# displayboard.net
KiCad netlist of a schematic drawn in EAGLE
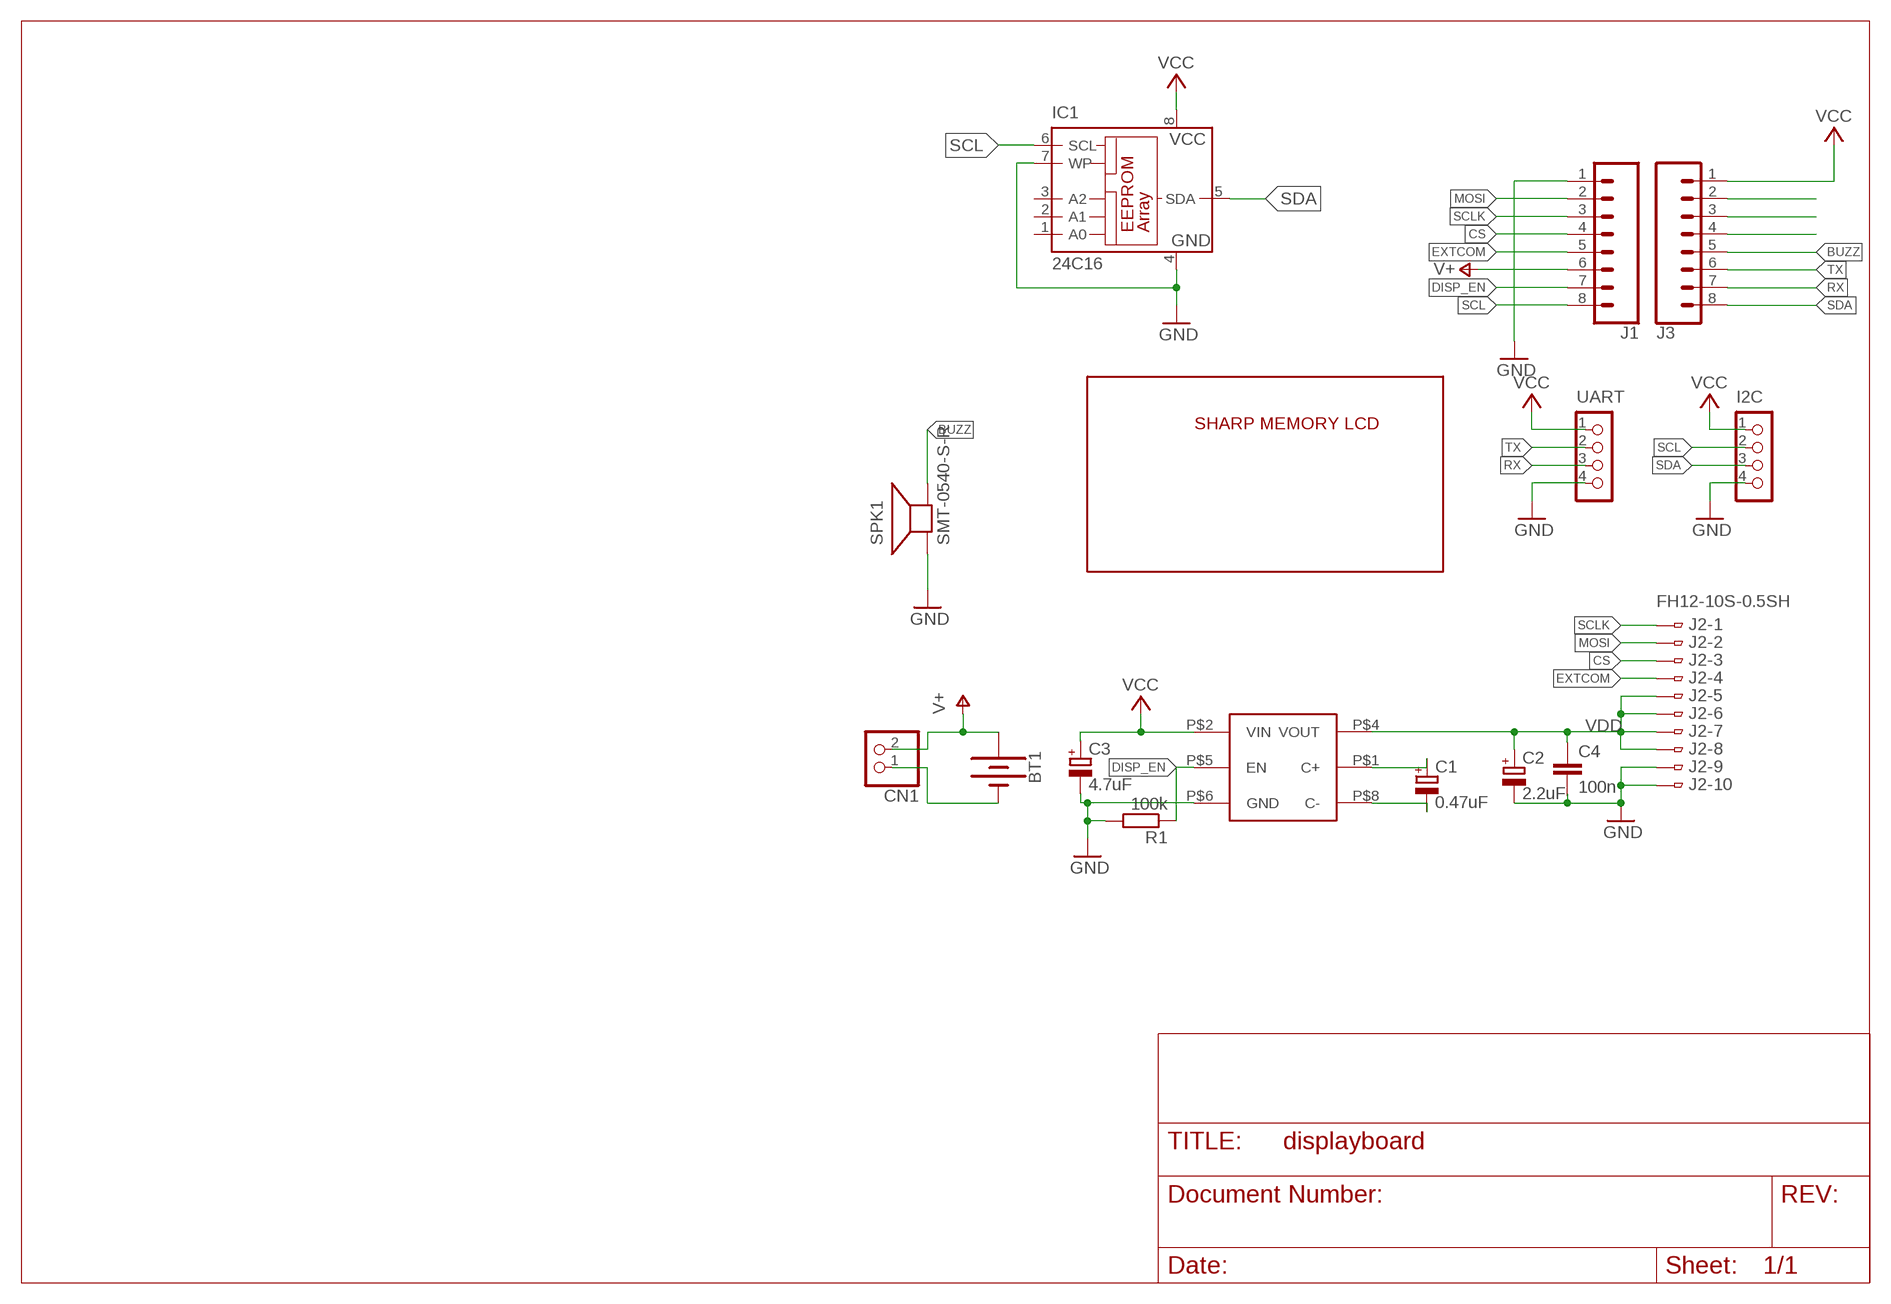
[diagram p0: schematic, sheet 1]

(export (version "E")
  (design (tool "Eeschema 10.0.6"))
  (components
    (comp (ref "BT1")
      (value "BATTERY-18650")
      (footprint "eagle-import:BATTERY_18650-HOLDER")
      (libsource (lib "eagle-import") (part "BATTERY-18650"))
    )
    (comp (ref "C1")
      (value "0.47uF")
      (footprint "eagle-import:C_6032-28R")
      (libsource (lib "eagle-import") (part "CPOL-EUC/6032-28R"))
    )
    (comp (ref "C2")
      (value "2.2uF")
      (footprint "eagle-import:C_6032-28R")
      (libsource (lib "eagle-import") (part "CPOL-EUC/6032-28R"))
    )
    (comp (ref "C3")
      (value "4.7uF")
      (footprint "eagle-import:C_6032-28R")
      (libsource (lib "eagle-import") (part "CPOL-EUC/6032-28R"))
    )
    (comp (ref "C4")
      (value "100n")
      (footprint "eagle-import:C1206K")
      (libsource (lib "eagle-import") (part "C-EUC1206K"))
    )
    (comp (ref "CN1")
      (value "PINHD-1X2")
      (footprint "eagle-import:1X02")
      (libsource (lib "eagle-import") (part "PINHD-1X2"))
    )
    (comp (ref "I2C")
      (value "CON_HEADER_1X04")
      (footprint "eagle-import:M1X4")
      (libsource (lib "eagle-import") (part "CON_HEADER_1X04"))
    )
    (comp (ref "IC1")
      (value "24C16")
      (footprint "eagle-import:SO-08")
      (fields (field (name "MPN") "M24C04-WMN6P"))
      (libsource (lib "eagle-import") (part "24CSN04"))
    )
    (comp (ref "J1")
      (value "CONN_08SMD-COMBO-FEMALE")
      (footprint "eagle-import:1X08_SMD_COMBINED")
      (libsource (lib "eagle-import") (part "CONN_08SMD-COMBO-FEMALE"))
    )
    (comp (ref "J2")
      (value "FH12-10S-0.5SH")
      (footprint "eagle-import:FH12-10S-0.5SH")
      (fields (field (name "MPN") "FH12-10S-0.5SH(55)"))
      (libsource (lib "eagle-import") (part "FH12-10S-0.5SH"))
    )
    (comp (ref "J3")
      (value "CONN_08SMD-COMBO-FEMALE")
      (footprint "eagle-import:1X08_SMD_COMBINED")
      (libsource (lib "eagle-import") (part "CONN_08SMD-COMBO-FEMALE"))
    )
    (comp (ref "R1")
      (value "100k")
      (footprint "eagle-import:R0805")
      (libsource (lib "eagle-import") (part "R-EU_R0805"))
    )
    (comp (ref "SPK1")
      (value "SMT-0540-S-R")
      (footprint "eagle-import:SMT-0540-S-R")
      (libsource (lib "eagle-import") (part "SMT-0540-S-R"))
    )
    (comp (ref "U$1")
      (value "S8821")
      (footprint "eagle-import:SNT-8A")
      (libsource (lib "eagle-import") (part "S8821"))
    )
    (comp (ref "U$2")
      (value "MEMORYLCD")
      (footprint "eagle-import:LS027B7DH01")
      (libsource (lib "eagle-import") (part "MEMORYLCD"))
    )
    (comp (ref "UART")
      (value "CON_HEADER_1X04")
      (footprint "eagle-import:M1X4")
      (libsource (lib "eagle-import") (part "CON_HEADER_1X04"))
    )
  )
  (nets
    (net (code "1") (name "/VDD") (class "Default")
      (node (ref "C2") (pin "+") (pinfunction "+_+") (pintype "passive"))
      (node (ref "C4") (pin "1") (pinfunction "1_1") (pintype "passive"))
      (node (ref "J2") (pin "5") (pinfunction "1_5") (pintype "passive"))
      (node (ref "J2") (pin "6") (pinfunction "1_6") (pintype "passive"))
      (node (ref "J2") (pin "7") (pinfunction "1_7") (pintype "passive"))
      (node (ref "J2") (pin "8") (pinfunction "1_8") (pintype "passive"))
      (node (ref "U$1") (pin "P$4") (pinfunction "VOUT_P$4") (pintype "bidirectional"))
    )
    (net (code "2") (name "BUZZ") (class "Default")
      (node (ref "J3") (pin "5") (pinfunction "5_5") (pintype "passive"))
      (node (ref "SPK1") (pin "+") (pinfunction "-_+") (pintype "passive"))
    )
    (net (code "3") (name "CS") (class "Default")
      (node (ref "J1") (pin "4") (pinfunction "4_4") (pintype "passive"))
      (node (ref "J2") (pin "3") (pinfunction "1_3") (pintype "passive"))
    )
    (net (code "4") (name "DISP_EN") (class "Default")
      (node (ref "J1") (pin "7") (pinfunction "7_7") (pintype "passive"))
      (node (ref "R1") (pin "1") (pinfunction "1_1") (pintype "passive"))
      (node (ref "U$1") (pin "P$5") (pinfunction "EN_P$5") (pintype "bidirectional"))
    )
    (net (code "5") (name "EXTCOM") (class "Default")
      (node (ref "J1") (pin "5") (pinfunction "5_5") (pintype "passive"))
      (node (ref "J2") (pin "4") (pinfunction "1_4") (pintype "passive"))
    )
    (net (code "6") (name "GND") (class "Default")
      (node (ref "C2") (pin "-") (pinfunction "-_-") (pintype "passive"))
      (node (ref "C3") (pin "-") (pinfunction "-_-") (pintype "passive"))
      (node (ref "C4") (pin "2") (pinfunction "2_2") (pintype "passive"))
      (node (ref "I2C") (pin "4") (pinfunction "4_4") (pintype "bidirectional"))
      (node (ref "IC1") (pin "4") (pinfunction "GND_4") (pintype "power_in"))
      (node (ref "IC1") (pin "7") (pinfunction "WP_7") (pintype "input"))
      (node (ref "J1") (pin "1") (pinfunction "1_1") (pintype "passive"))
      (node (ref "J2") (pin "10") (pinfunction "1_10") (pintype "passive"))
      (node (ref "J2") (pin "9") (pinfunction "1_9") (pintype "passive"))
      (node (ref "R1") (pin "2") (pinfunction "2_2") (pintype "passive"))
      (node (ref "SPK1") (pin "-") (pinfunction "+_-") (pintype "passive"))
      (node (ref "U$1") (pin "P$6") (pinfunction "GND_P$6") (pintype "bidirectional"))
      (node (ref "UART") (pin "4") (pinfunction "4_4") (pintype "bidirectional"))
    )
    (net (code "7") (name "MOSI") (class "Default")
      (node (ref "J1") (pin "2") (pinfunction "2_2") (pintype "passive"))
      (node (ref "J2") (pin "2") (pinfunction "1_2") (pintype "passive"))
    )
    (net (code "8") (name "Net-(BT1--)") (class "Default")
      (node (ref "BT1") (pin "GND@1") (pinfunction "-_GND@1") (pintype "power_in"))
      (node (ref "CN1") (pin "1") (pinfunction "1_1") (pintype "passive"))
    )
    (net (code "9") (name "Net-(U$1-C+)") (class "Default")
      (node (ref "C1") (pin "+") (pinfunction "+_+") (pintype "passive"))
      (node (ref "U$1") (pin "P$1") (pinfunction "C+_P$1") (pintype "bidirectional"))
    )
    (net (code "10") (name "Net-(U$1-C-)") (class "Default")
      (node (ref "C1") (pin "-") (pinfunction "-_-") (pintype "passive"))
      (node (ref "U$1") (pin "P$8") (pinfunction "C-_P$8") (pintype "bidirectional"))
    )
    (net (code "11") (name "RX") (class "Default")
      (node (ref "J3") (pin "7") (pinfunction "7_7") (pintype "passive"))
      (node (ref "UART") (pin "3") (pinfunction "3_3") (pintype "bidirectional"))
    )
    (net (code "12") (name "SCL") (class "Default")
      (node (ref "I2C") (pin "2") (pinfunction "2_2") (pintype "bidirectional"))
      (node (ref "IC1") (pin "6") (pinfunction "SCL_6") (pintype "input"))
      (node (ref "J1") (pin "8") (pinfunction "8_8") (pintype "passive"))
    )
    (net (code "13") (name "SCLK") (class "Default")
      (node (ref "J1") (pin "3") (pinfunction "3_3") (pintype "passive"))
      (node (ref "J2") (pin "1") (pinfunction "1_1") (pintype "passive"))
    )
    (net (code "14") (name "SDA") (class "Default")
      (node (ref "I2C") (pin "3") (pinfunction "3_3") (pintype "bidirectional"))
      (node (ref "IC1") (pin "5") (pinfunction "SDA_5") (pintype "bidirectional"))
      (node (ref "J3") (pin "8") (pinfunction "8_8") (pintype "passive"))
    )
    (net (code "15") (name "TX") (class "Default")
      (node (ref "J3") (pin "6") (pinfunction "6_6") (pintype "passive"))
      (node (ref "UART") (pin "2") (pinfunction "2_2") (pintype "bidirectional"))
    )
    (net (code "16") (name "V+") (class "Default")
      (node (ref "BT1") (pin "PWR@1") (pinfunction "+_PWR@1") (pintype "power_in"))
      (node (ref "CN1") (pin "2") (pinfunction "2_2") (pintype "passive"))
      (node (ref "J1") (pin "6") (pinfunction "6_6") (pintype "passive"))
    )
    (net (code "17") (name "VCC") (class "Default")
      (node (ref "C3") (pin "+") (pinfunction "+_+") (pintype "passive"))
      (node (ref "I2C") (pin "1") (pinfunction "1_1") (pintype "bidirectional"))
      (node (ref "IC1") (pin "8") (pinfunction "VCC_8") (pintype "power_in"))
      (node (ref "J3") (pin "1") (pinfunction "1_1") (pintype "passive"))
      (node (ref "U$1") (pin "P$2") (pinfunction "VIN_P$2") (pintype "bidirectional"))
      (node (ref "UART") (pin "1") (pinfunction "1_1") (pintype "bidirectional"))
    )
    (net (code "18") (name "unconnected-(IC1-A0-Pad1)") (class "Default")
      (node (ref "IC1") (pin "1") (pinfunction "A0_1") (pintype "input"))
    )
    (net (code "19") (name "unconnected-(IC1-A1-Pad2)") (class "Default")
      (node (ref "IC1") (pin "2") (pinfunction "A1_2") (pintype "input"))
    )
    (net (code "20") (name "unconnected-(IC1-A2-Pad3)") (class "Default")
      (node (ref "IC1") (pin "3") (pinfunction "A2_3") (pintype "input"))
    )
    (net (code "21") (name "unconnected-(J3-Pad2)") (class "Default")
      (node (ref "J3") (pin "2") (pinfunction "2_2") (pintype "passive"))
    )
    (net (code "22") (name "unconnected-(J3-Pad3)") (class "Default")
      (node (ref "J3") (pin "3") (pinfunction "3_3") (pintype "passive"))
    )
    (net (code "23") (name "unconnected-(J3-Pad4)") (class "Default")
      (node (ref "J3") (pin "4") (pinfunction "4_4") (pintype "passive"))
    )
  )
)
